# 06_-_BUTTONS_-_LEDS.net
KiCad netlist of a schematic drawn in Altium Designer
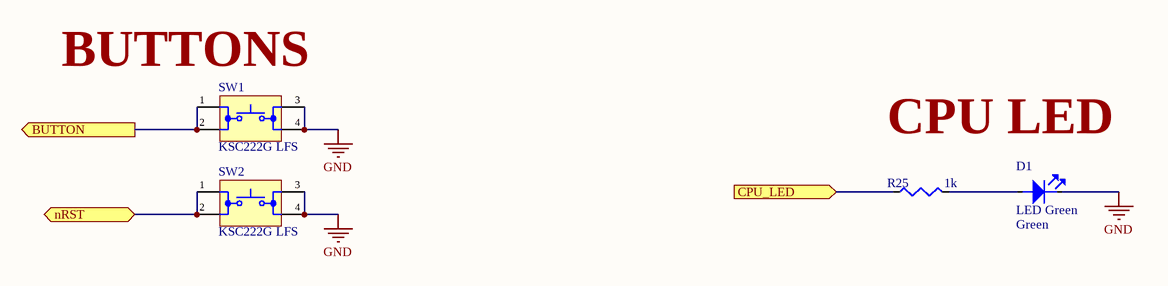
[diagram p0: [06] - BUTTONS - LEDS.SchDoc]

(export (version "E")
  (design (tool "Eeschema 10.0.6"))
  (components
    (comp (ref "D1")
      (value "LED Green")
      (footprint "L0603 GREEN")
      (description "LED 0603 Green")
      (fields (field (name "COLOR") "Green"))
      (libsource (lib "Passive components") (part "HSMG-C196"))
    )
    (comp (ref "R25")
      (value "1k")
      (footprint "R0603")
      (description "R0603")
      (fields (field (name "Comment") "CPF-A-0603B100KE1"))
      (libsource (lib "Passive components") (part "CPF-A-0603B100KE1"))
    )
    (comp (ref "SW1")
      (value "KSC222G LFS")
      (footprint "KSC222G LFS")
      (description "Button SMD")
      (libsource (lib "Sensors") (part "KSC222G LFS"))
    )
    (comp (ref "SW2")
      (value "KSC222G LFS")
      (footprint "KSC222G LFS")
      (description "Button SMD")
      (libsource (lib "Sensors") (part "KSC222G LFS"))
    )
  )
  (nets
    (net (code "1") (name "/BUTTON") (class "Default")
      (node (ref "SW1") (pin "1") (pinfunction "1_1") (pintype "passive"))
      (node (ref "SW1") (pin "2") (pinfunction "2_2") (pintype "passive"))
    )
    (net (code "2") (name "/CPU_LED") (class "Default")
      (node (ref "R25") (pin "1") (pinfunction "1_1") (pintype "passive"))
    )
    (net (code "3") (name "/nRST") (class "Default")
      (node (ref "SW2") (pin "1") (pinfunction "1_1") (pintype "passive"))
      (node (ref "SW2") (pin "2") (pinfunction "2_2") (pintype "passive"))
    )
    (net (code "4") (name "GND") (class "Default")
      (node (ref "D1") (pin "2") (pinfunction "2_2") (pintype "passive"))
      (node (ref "SW1") (pin "3") (pinfunction "3_3") (pintype "passive"))
      (node (ref "SW1") (pin "4") (pinfunction "4_4") (pintype "passive"))
      (node (ref "SW2") (pin "3") (pinfunction "3_3") (pintype "passive"))
      (node (ref "SW2") (pin "4") (pinfunction "4_4") (pintype "passive"))
    )
    (net (code "5") (name "Net-(D1-Pad1)") (class "Default")
      (node (ref "D1") (pin "1") (pinfunction "1_1") (pintype "passive"))
      (node (ref "R25") (pin "2") (pinfunction "2_2") (pintype "passive"))
    )
  )
)
